# Connectors.net
KiCad netlist of a schematic drawn in Altium Designer
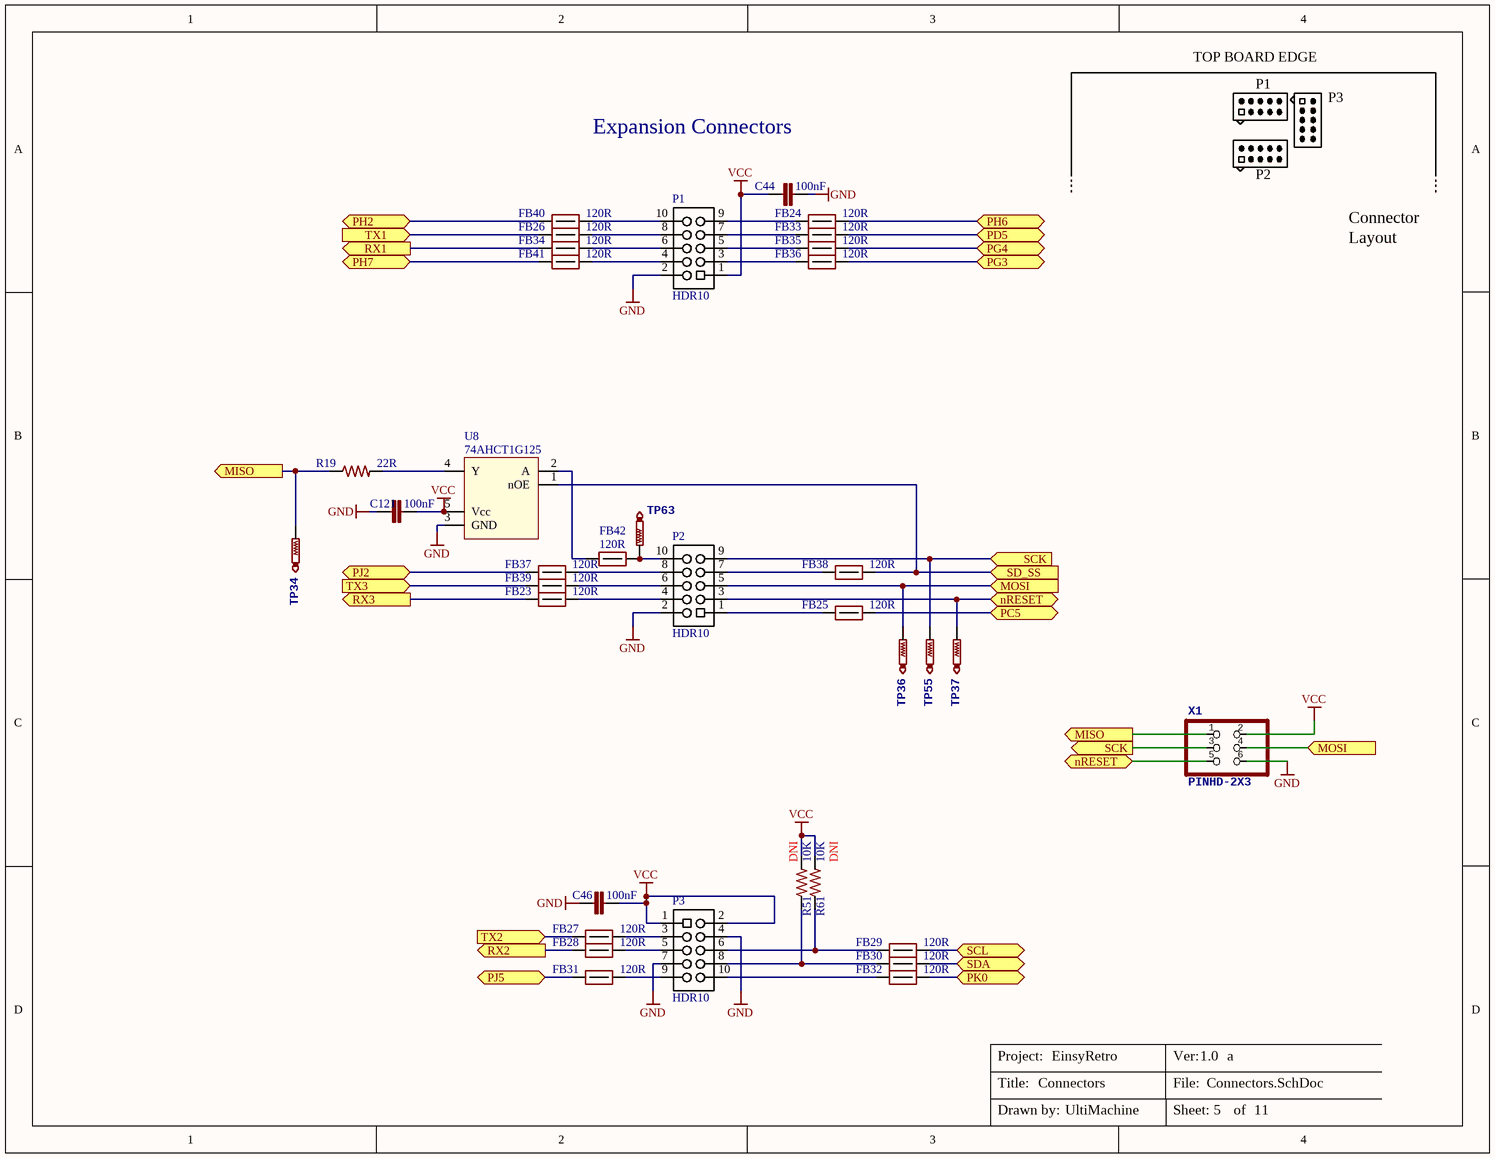
[diagram p0: Connectors.SchDoc]

(export (version "E")
  (design (tool "Eeschema 10.0.6"))
  (components
    (comp (ref "C44")
      (value "100nF")
      (footprint "C0402")
      (description "CAP CER 0402 100nF 16V 10% X7R")
      (fields (field (name "MANUFACTURER") "Murata") (field (name "TOLERANCE") "+/- 10%"))
      (libsource (lib "3Delight") (part "GRM155R71C104KA88D"))
    )
    (comp (ref "C46")
      (value "100nF")
      (footprint "C0402")
      (description "CAP CER 0402 100nF 16V 10% X7R")
      (fields (field (name "MANUFACTURER") "Murata") (field (name "TOLERANCE") "+/- 10%"))
      (libsource (lib "3Delight") (part "GRM155R71C104KA88D"))
    )
    (comp (ref "C121")
      (value "100nF")
      (footprint "C0402")
      (description "CAP CER 0402 100nF 16V 10% X7R")
      (fields (field (name "MANUFACTURER") "Murata") (field (name "TOLERANCE") "+/- 10%"))
      (libsource (lib "3Delight") (part "GRM155R71C104KA88D"))
    )
    (comp (ref "FB23")
      (value "120R")
      (footprint "R0402")
      (description "FERRITE BEAD 120 OHM 0402 1LN")
      (fields (field (name "MANUFACTURER") "Taiyo Yuden") (field (name "PART") "FERRITE 120R 1A 0402"))
      (libsource (lib "Inductors") (part "FERRITE 120R 1A 0402"))
    )
    (comp (ref "FB24")
      (value "120R")
      (footprint "R0402")
      (description "FERRITE BEAD 120 OHM 0402 1LN")
      (fields (field (name "MANUFACTURER") "Taiyo Yuden") (field (name "PART") "FERRITE 120R 1A 0402"))
      (libsource (lib "Inductors") (part "FERRITE 120R 1A 0402"))
    )
    (comp (ref "FB25")
      (value "120R")
      (footprint "R0402")
      (description "FERRITE BEAD 120 OHM 0402 1LN")
      (fields (field (name "MANUFACTURER") "Taiyo Yuden") (field (name "PART") "FERRITE 120R 1A 0402"))
      (libsource (lib "Inductors") (part "FERRITE 120R 1A 0402"))
    )
    (comp (ref "FB26")
      (value "120R")
      (footprint "R0402")
      (description "FERRITE BEAD 120 OHM 0402 1LN")
      (fields (field (name "MANUFACTURER") "Taiyo Yuden") (field (name "PART") "FERRITE 120R 1A 0402"))
      (libsource (lib "Inductors") (part "FERRITE 120R 1A 0402"))
    )
    (comp (ref "FB27")
      (value "120R")
      (footprint "R0402")
      (description "FERRITE BEAD 120 OHM 0402 1LN")
      (fields (field (name "MANUFACTURER") "Taiyo Yuden") (field (name "PART") "FERRITE 120R 1A 0402"))
      (libsource (lib "Inductors") (part "FERRITE 120R 1A 0402"))
    )
    (comp (ref "FB28")
      (value "120R")
      (footprint "R0402")
      (description "FERRITE BEAD 120 OHM 0402 1LN")
      (fields (field (name "MANUFACTURER") "Taiyo Yuden") (field (name "PART") "FERRITE 120R 1A 0402"))
      (libsource (lib "Inductors") (part "FERRITE 120R 1A 0402"))
    )
    (comp (ref "FB29")
      (value "120R")
      (footprint "R0402")
      (description "FERRITE BEAD 120 OHM 0402 1LN")
      (fields (field (name "MANUFACTURER") "Taiyo Yuden") (field (name "PART") "FERRITE 120R 1A 0402"))
      (libsource (lib "Inductors") (part "FERRITE 120R 1A 0402"))
    )
    (comp (ref "FB30")
      (value "120R")
      (footprint "R0402")
      (description "FERRITE BEAD 120 OHM 0402 1LN")
      (fields (field (name "MANUFACTURER") "Taiyo Yuden") (field (name "PART") "FERRITE 120R 1A 0402"))
      (libsource (lib "Inductors") (part "FERRITE 120R 1A 0402"))
    )
    (comp (ref "FB31")
      (value "120R")
      (footprint "R0402")
      (description "FERRITE BEAD 120 OHM 0402 1LN")
      (fields (field (name "MANUFACTURER") "Taiyo Yuden") (field (name "PART") "FERRITE 120R 1A 0402"))
      (libsource (lib "Inductors") (part "FERRITE 120R 1A 0402"))
    )
    (comp (ref "FB32")
      (value "120R")
      (footprint "R0402")
      (description "FERRITE BEAD 120 OHM 0402 1LN")
      (fields (field (name "MANUFACTURER") "Taiyo Yuden") (field (name "PART") "FERRITE 120R 1A 0402"))
      (libsource (lib "Inductors") (part "FERRITE 120R 1A 0402"))
    )
    (comp (ref "FB33")
      (value "120R")
      (footprint "R0402")
      (description "FERRITE BEAD 120 OHM 0402 1LN")
      (fields (field (name "MANUFACTURER") "Taiyo Yuden") (field (name "PART") "FERRITE 120R 1A 0402"))
      (libsource (lib "Inductors") (part "FERRITE 120R 1A 0402"))
    )
    (comp (ref "FB34")
      (value "120R")
      (footprint "R0402")
      (description "FERRITE BEAD 120 OHM 0402 1LN")
      (fields (field (name "MANUFACTURER") "Taiyo Yuden") (field (name "PART") "FERRITE 120R 1A 0402"))
      (libsource (lib "Inductors") (part "FERRITE 120R 1A 0402"))
    )
    (comp (ref "FB35")
      (value "120R")
      (footprint "R0402")
      (description "FERRITE BEAD 120 OHM 0402 1LN")
      (fields (field (name "MANUFACTURER") "Taiyo Yuden") (field (name "PART") "FERRITE 120R 1A 0402"))
      (libsource (lib "Inductors") (part "FERRITE 120R 1A 0402"))
    )
    (comp (ref "FB36")
      (value "120R")
      (footprint "R0402")
      (description "FERRITE BEAD 120 OHM 0402 1LN")
      (fields (field (name "MANUFACTURER") "Taiyo Yuden") (field (name "PART") "FERRITE 120R 1A 0402"))
      (libsource (lib "Inductors") (part "FERRITE 120R 1A 0402"))
    )
    (comp (ref "FB37")
      (value "120R")
      (footprint "R0402")
      (description "FERRITE BEAD 120 OHM 0402 1LN")
      (fields (field (name "MANUFACTURER") "Taiyo Yuden") (field (name "PART") "FERRITE 120R 1A 0402"))
      (libsource (lib "Inductors") (part "FERRITE 120R 1A 0402"))
    )
    (comp (ref "FB38")
      (value "120R")
      (footprint "R0402")
      (description "FERRITE BEAD 120 OHM 0402 1LN")
      (fields (field (name "MANUFACTURER") "Taiyo Yuden") (field (name "PART") "FERRITE 120R 1A 0402"))
      (libsource (lib "Inductors") (part "FERRITE 120R 1A 0402"))
    )
    (comp (ref "FB39")
      (value "120R")
      (footprint "R0402")
      (description "FERRITE BEAD 120 OHM 0402 1LN")
      (fields (field (name "MANUFACTURER") "Taiyo Yuden") (field (name "PART") "FERRITE 120R 1A 0402"))
      (libsource (lib "Inductors") (part "FERRITE 120R 1A 0402"))
    )
    (comp (ref "FB40")
      (value "120R")
      (footprint "R0402")
      (description "FERRITE BEAD 120 OHM 0402 1LN")
      (fields (field (name "MANUFACTURER") "Taiyo Yuden") (field (name "PART") "FERRITE 120R 1A 0402"))
      (libsource (lib "Inductors") (part "FERRITE 120R 1A 0402"))
    )
    (comp (ref "FB41")
      (value "120R")
      (footprint "R0402")
      (description "FERRITE BEAD 120 OHM 0402 1LN")
      (fields (field (name "MANUFACTURER") "Taiyo Yuden") (field (name "PART") "FERRITE 120R 1A 0402"))
      (libsource (lib "Inductors") (part "FERRITE 120R 1A 0402"))
    )
    (comp (ref "FB42")
      (value "120R")
      (footprint "R0402")
      (description "FERRITE BEAD 120 OHM 0402 1LN")
      (fields (field (name "MANUFACTURER") "Taiyo Yuden") (field (name "PART") "FERRITE 120R 1A 0402"))
      (libsource (lib "Inductors") (part "FERRITE 120R 1A 0402"))
    )
    (comp (ref "P1")
      (value "HDR10")
      (footprint "HDR2X5 IDC")
      (description "CONN HEADER VERT 10POS GOLD")
      (fields (field (name "MANUFACTURER") "On Shore") (field (name "TOLERANCE") "-NA-"))
      (libsource (lib "") (part "Header 10PIN 2ROW T-HOLE VERT SHROUDED_1"))
    )
    (comp (ref "P2")
      (value "HDR10")
      (footprint "HDR2X5 IDC")
      (description "CONN HEADER VERT 10POS GOLD")
      (fields (field (name "MANUFACTURER") "On Shore") (field (name "TOLERANCE") "-NA-"))
      (libsource (lib "") (part "Header 10PIN 2ROW T-HOLE VERT SHROUDED_1"))
    )
    (comp (ref "P3")
      (value "HDR10")
      (footprint "HDR2X5 IDC THIEVING")
      (description "CONN HEADER VERT 10POS GOLD")
      (fields (field (name "MANUFACTURER") "On Shore") (field (name "TOLERANCE") "-NA-"))
      (libsource (lib "Connectors") (part "Header 10PIN 2ROW T-HOLE VERT SHROUDED"))
    )
    (comp (ref "R19")
      (value "22R")
      (footprint "R0402")
      (description "RES 0402 22r 62.5mW 1%")
      (fields (field (name "MANUFACTURER") "Yageo") (field (name "TOLERANCE") "+/- 1%"))
      (libsource (lib "3Delight") (part "RC0402FR-0722RL"))
    )
    (comp (ref "R51")
      (value "10K")
      (footprint "R0402")
      (description "RES SMD 10K OHM 1% 1/16W 0402")
      (fields
        (field (name "MANUFACTURER") "Yageo")
        (field (name "PART") "10k 1% 0402")
        (field (name "DNI") "DNI")
      )
      (libsource (lib "3Delight") (part "RC0402FR-0710KP"))
    )
    (comp (ref "R61")
      (value "10K")
      (footprint "R0402")
      (description "RES SMD 10K OHM 1% 1/16W 0402")
      (fields
        (field (name "MANUFACTURER") "Yageo")
        (field (name "PART") "10k 1% 0402")
        (field (name "DNI") "DNI")
      )
      (libsource (lib "3Delight") (part "RC0402FR-0710KP"))
    )
    (comp (ref "TP34")
      (value "TestPoint")
      (footprint "TP1-27")
      (description "Test Point")
      (libsource (lib "3Delight") (part "TestPoint"))
    )
    (comp (ref "TP36")
      (value "TestPoint")
      (footprint "TP1-27")
      (description "Test Point")
      (libsource (lib "3Delight") (part "TestPoint"))
    )
    (comp (ref "TP37")
      (value "TestPoint")
      (footprint "TP1-27")
      (description "Test Point")
      (libsource (lib "3Delight") (part "TestPoint"))
    )
    (comp (ref "TP55")
      (value "TestPoint")
      (footprint "TP1-27")
      (description "Test Point")
      (libsource (lib "3Delight") (part "TestPoint"))
    )
    (comp (ref "TP63")
      (value "TestPoint")
      (footprint "TP1-27")
      (description "Test Point")
      (libsource (lib "") (part "TestPoint_1"))
    )
    (comp (ref "U8")
      (value "74AHCT1G125")
      (footprint "SOTFL50P160X60-5L")
      (description "IC BUS BUFF TRI-ST N-INV  SOT-553")
      (fields (field (name "TOLERANCE") "-NA-") (field (name "MANUFACTURER") "TI"))
      (libsource (lib "ICs-Logic") (part "SN74AHCT1G125DRLR"))
    )
    (comp (ref "X1")
      (value "PINHD-2X3")
      (footprint "2X03")
      (description "CONN HEADER VERT 6POS GOLD")
      (fields (field (name "MANUFACTURER") "MultiComp") (field (name "PART") "6PIN"))
      (libsource (lib "Connectors") (part "PINHD-2X3"))
    )
  )
  (nets
    (net (code "1") (name "/MISO") (class "Default")
      (node (ref "R19") (pin "1") (pinfunction "1_1") (pintype "passive"))
      (node (ref "TP34") (pin "TP") (pinfunction "TP_TP") (pintype "passive"))
      (node (ref "X1") (pin "1") (pinfunction "1_1") (pintype "passive"))
    )
    (net (code "2") (name "/MOSI") (class "Default")
      (node (ref "P2") (pin "5") (pinfunction "5_5") (pintype "passive"))
      (node (ref "TP36") (pin "TP") (pinfunction "TP_TP") (pintype "passive"))
      (node (ref "X1") (pin "4") (pinfunction "4_4") (pintype "passive"))
    )
    (net (code "3") (name "/PC5") (class "Default")
      (node (ref "FB25") (pin "2") (pinfunction "2_2") (pintype "passive"))
    )
    (net (code "4") (name "/PD5") (class "Default")
      (node (ref "FB33") (pin "2") (pinfunction "2_2") (pintype "passive"))
    )
    (net (code "5") (name "/PG3") (class "Default")
      (node (ref "FB36") (pin "2") (pinfunction "2_2") (pintype "passive"))
    )
    (net (code "6") (name "/PG4") (class "Default")
      (node (ref "FB35") (pin "2") (pinfunction "2_2") (pintype "passive"))
    )
    (net (code "7") (name "/PH2") (class "Default")
      (node (ref "FB40") (pin "1") (pinfunction "1_1") (pintype "passive"))
    )
    (net (code "8") (name "/PH6") (class "Default")
      (node (ref "FB24") (pin "2") (pinfunction "2_2") (pintype "passive"))
    )
    (net (code "9") (name "/PH7") (class "Default")
      (node (ref "FB41") (pin "1") (pinfunction "1_1") (pintype "passive"))
    )
    (net (code "10") (name "/PJ2") (class "Default")
      (node (ref "FB37") (pin "1") (pinfunction "1_1") (pintype "passive"))
    )
    (net (code "11") (name "/PJ5") (class "Default")
      (node (ref "FB31") (pin "1") (pinfunction "1_1") (pintype "passive"))
    )
    (net (code "12") (name "/PK0") (class "Default")
      (node (ref "FB32") (pin "2") (pinfunction "2_2") (pintype "passive"))
    )
    (net (code "13") (name "/RX1") (class "Default")
      (node (ref "FB34") (pin "1") (pinfunction "1_1") (pintype "passive"))
    )
    (net (code "14") (name "/RX2") (class "Default")
      (node (ref "FB28") (pin "1") (pinfunction "1_1") (pintype "passive"))
    )
    (net (code "15") (name "/RX3") (class "Default")
      (node (ref "FB23") (pin "1") (pinfunction "1_1") (pintype "passive"))
    )
    (net (code "16") (name "/SCK") (class "Default")
      (node (ref "P2") (pin "9") (pinfunction "9_9") (pintype "passive"))
      (node (ref "TP55") (pin "TP") (pinfunction "TP_TP") (pintype "passive"))
      (node (ref "X1") (pin "3") (pinfunction "3_3") (pintype "passive"))
    )
    (net (code "17") (name "/SCL") (class "Default")
      (node (ref "FB29") (pin "2") (pinfunction "2_2") (pintype "passive"))
    )
    (net (code "18") (name "/SDA") (class "Default")
      (node (ref "FB30") (pin "2") (pinfunction "2_2") (pintype "passive"))
    )
    (net (code "19") (name "/SD_SS") (class "Default")
      (node (ref "FB38") (pin "2") (pinfunction "2_2") (pintype "passive"))
      (node (ref "U8") (pin "1") (pinfunction "nOE_1") (pintype "passive"))
    )
    (net (code "20") (name "/TX1") (class "Default")
      (node (ref "FB26") (pin "1") (pinfunction "1_1") (pintype "passive"))
    )
    (net (code "21") (name "/TX2") (class "Default")
      (node (ref "FB27") (pin "1") (pinfunction "1_1") (pintype "passive"))
    )
    (net (code "22") (name "/TX3") (class "Default")
      (node (ref "FB39") (pin "1") (pinfunction "1_1") (pintype "passive"))
    )
    (net (code "23") (name "/nRESET") (class "Default")
      (node (ref "P2") (pin "3") (pinfunction "3_3") (pintype "passive"))
      (node (ref "TP37") (pin "TP") (pinfunction "TP_TP") (pintype "passive"))
      (node (ref "X1") (pin "5") (pinfunction "5_5") (pintype "passive"))
    )
    (net (code "24") (name "GND") (class "Default")
      (node (ref "C121") (pin "1") (pinfunction "1_1") (pintype "passive"))
      (node (ref "C44") (pin "2") (pinfunction "2_2") (pintype "passive"))
      (node (ref "C46") (pin "1") (pinfunction "1_1") (pintype "passive"))
      (node (ref "P1") (pin "2") (pinfunction "2_2") (pintype "passive"))
      (node (ref "P2") (pin "2") (pinfunction "2_2") (pintype "passive"))
      (node (ref "P3") (pin "4") (pinfunction "4_4") (pintype "passive"))
      (node (ref "P3") (pin "7") (pinfunction "7_7") (pintype "passive"))
      (node (ref "U8") (pin "3") (pinfunction "GND_3") (pintype "passive"))
      (node (ref "X1") (pin "6") (pinfunction "6_6") (pintype "passive"))
    )
    (net (code "25") (name "Net-(FB23-Pad2)") (class "Default")
      (node (ref "FB23") (pin "2") (pinfunction "2_2") (pintype "passive"))
      (node (ref "P2") (pin "4") (pinfunction "4_4") (pintype "passive"))
    )
    (net (code "26") (name "Net-(FB24-Pad1)") (class "Default")
      (node (ref "FB24") (pin "1") (pinfunction "1_1") (pintype "passive"))
      (node (ref "P1") (pin "9") (pinfunction "9_9") (pintype "passive"))
    )
    (net (code "27") (name "Net-(FB25-Pad1)") (class "Default")
      (node (ref "FB25") (pin "1") (pinfunction "1_1") (pintype "passive"))
      (node (ref "P2") (pin "1") (pinfunction "1_1") (pintype "passive"))
    )
    (net (code "28") (name "Net-(FB26-Pad2)") (class "Default")
      (node (ref "FB26") (pin "2") (pinfunction "2_2") (pintype "passive"))
      (node (ref "P1") (pin "8") (pinfunction "8_8") (pintype "passive"))
    )
    (net (code "29") (name "Net-(FB27-Pad2)") (class "Default")
      (node (ref "FB27") (pin "2") (pinfunction "2_2") (pintype "passive"))
      (node (ref "P3") (pin "3") (pinfunction "3_3") (pintype "passive"))
    )
    (net (code "30") (name "Net-(FB28-Pad2)") (class "Default")
      (node (ref "FB28") (pin "2") (pinfunction "2_2") (pintype "passive"))
      (node (ref "P3") (pin "5") (pinfunction "5_5") (pintype "passive"))
    )
    (net (code "31") (name "Net-(FB29-Pad1)") (class "Default")
      (node (ref "FB29") (pin "1") (pinfunction "1_1") (pintype "passive"))
      (node (ref "P3") (pin "6") (pinfunction "6_6") (pintype "passive"))
      (node (ref "R61") (pin "1") (pinfunction "1_1") (pintype "passive"))
    )
    (net (code "32") (name "Net-(FB30-Pad1)") (class "Default")
      (node (ref "FB30") (pin "1") (pinfunction "1_1") (pintype "passive"))
      (node (ref "P3") (pin "8") (pinfunction "8_8") (pintype "passive"))
      (node (ref "R51") (pin "1") (pinfunction "1_1") (pintype "passive"))
    )
    (net (code "33") (name "Net-(FB31-Pad2)") (class "Default")
      (node (ref "FB31") (pin "2") (pinfunction "2_2") (pintype "passive"))
      (node (ref "P3") (pin "9") (pinfunction "9_9") (pintype "passive"))
    )
    (net (code "34") (name "Net-(FB32-Pad1)") (class "Default")
      (node (ref "FB32") (pin "1") (pinfunction "1_1") (pintype "passive"))
      (node (ref "P3") (pin "10") (pinfunction "10_10") (pintype "passive"))
    )
    (net (code "35") (name "Net-(FB33-Pad1)") (class "Default")
      (node (ref "FB33") (pin "1") (pinfunction "1_1") (pintype "passive"))
      (node (ref "P1") (pin "7") (pinfunction "7_7") (pintype "passive"))
    )
    (net (code "36") (name "Net-(FB34-Pad2)") (class "Default")
      (node (ref "FB34") (pin "2") (pinfunction "2_2") (pintype "passive"))
      (node (ref "P1") (pin "6") (pinfunction "6_6") (pintype "passive"))
    )
    (net (code "37") (name "Net-(FB35-Pad1)") (class "Default")
      (node (ref "FB35") (pin "1") (pinfunction "1_1") (pintype "passive"))
      (node (ref "P1") (pin "5") (pinfunction "5_5") (pintype "passive"))
    )
    (net (code "38") (name "Net-(FB36-Pad1)") (class "Default")
      (node (ref "FB36") (pin "1") (pinfunction "1_1") (pintype "passive"))
      (node (ref "P1") (pin "3") (pinfunction "3_3") (pintype "passive"))
    )
    (net (code "39") (name "Net-(FB37-Pad2)") (class "Default")
      (node (ref "FB37") (pin "2") (pinfunction "2_2") (pintype "passive"))
      (node (ref "P2") (pin "8") (pinfunction "8_8") (pintype "passive"))
    )
    (net (code "40") (name "Net-(FB38-Pad1)") (class "Default")
      (node (ref "FB38") (pin "1") (pinfunction "1_1") (pintype "passive"))
      (node (ref "P2") (pin "7") (pinfunction "7_7") (pintype "passive"))
    )
    (net (code "41") (name "Net-(FB39-Pad2)") (class "Default")
      (node (ref "FB39") (pin "2") (pinfunction "2_2") (pintype "passive"))
      (node (ref "P2") (pin "6") (pinfunction "6_6") (pintype "passive"))
    )
    (net (code "42") (name "Net-(FB40-Pad2)") (class "Default")
      (node (ref "FB40") (pin "2") (pinfunction "2_2") (pintype "passive"))
      (node (ref "P1") (pin "10") (pinfunction "10_10") (pintype "passive"))
    )
    (net (code "43") (name "Net-(FB41-Pad2)") (class "Default")
      (node (ref "FB41") (pin "2") (pinfunction "2_2") (pintype "passive"))
      (node (ref "P1") (pin "4") (pinfunction "4_4") (pintype "passive"))
    )
    (net (code "44") (name "Net-(FB42-Pad2)") (class "Default")
      (node (ref "FB42") (pin "2") (pinfunction "2_2") (pintype "passive"))
      (node (ref "P2") (pin "10") (pinfunction "10_10") (pintype "passive"))
      (node (ref "TP63") (pin "TP") (pinfunction "TP_TP") (pintype "passive"))
    )
    (net (code "45") (name "Net-(U8-A)") (class "Default")
      (node (ref "FB42") (pin "1") (pinfunction "1_1") (pintype "passive"))
      (node (ref "U8") (pin "2") (pinfunction "A_2") (pintype "passive"))
    )
    (net (code "46") (name "Net-(U8-Y)") (class "Default")
      (node (ref "R19") (pin "2") (pinfunction "2_2") (pintype "passive"))
      (node (ref "U8") (pin "4") (pinfunction "Y_4") (pintype "passive"))
    )
    (net (code "47") (name "VCC") (class "Default")
      (node (ref "C121") (pin "2") (pinfunction "2_2") (pintype "passive"))
      (node (ref "C44") (pin "1") (pinfunction "1_1") (pintype "passive"))
      (node (ref "C46") (pin "2") (pinfunction "2_2") (pintype "passive"))
      (node (ref "P1") (pin "1") (pinfunction "1_1") (pintype "passive"))
      (node (ref "P3") (pin "1") (pinfunction "1_1") (pintype "passive"))
      (node (ref "P3") (pin "2") (pinfunction "2_2") (pintype "passive"))
      (node (ref "R51") (pin "2") (pinfunction "2_2") (pintype "passive"))
      (node (ref "R61") (pin "2") (pinfunction "2_2") (pintype "passive"))
      (node (ref "U8") (pin "5") (pinfunction "Vcc_5") (pintype "passive"))
      (node (ref "X1") (pin "2") (pinfunction "2_2") (pintype "passive"))
    )
    (net (code "48") (name "unconnected-(U8-NC-Pad23)") (class "Default")
      (node (ref "U8") (pin "23") (pinfunction "NC_23") (pintype "passive"))
    )
  )
)
